# Sheet2.net
KiCad netlist of a schematic drawn in Altium Designer
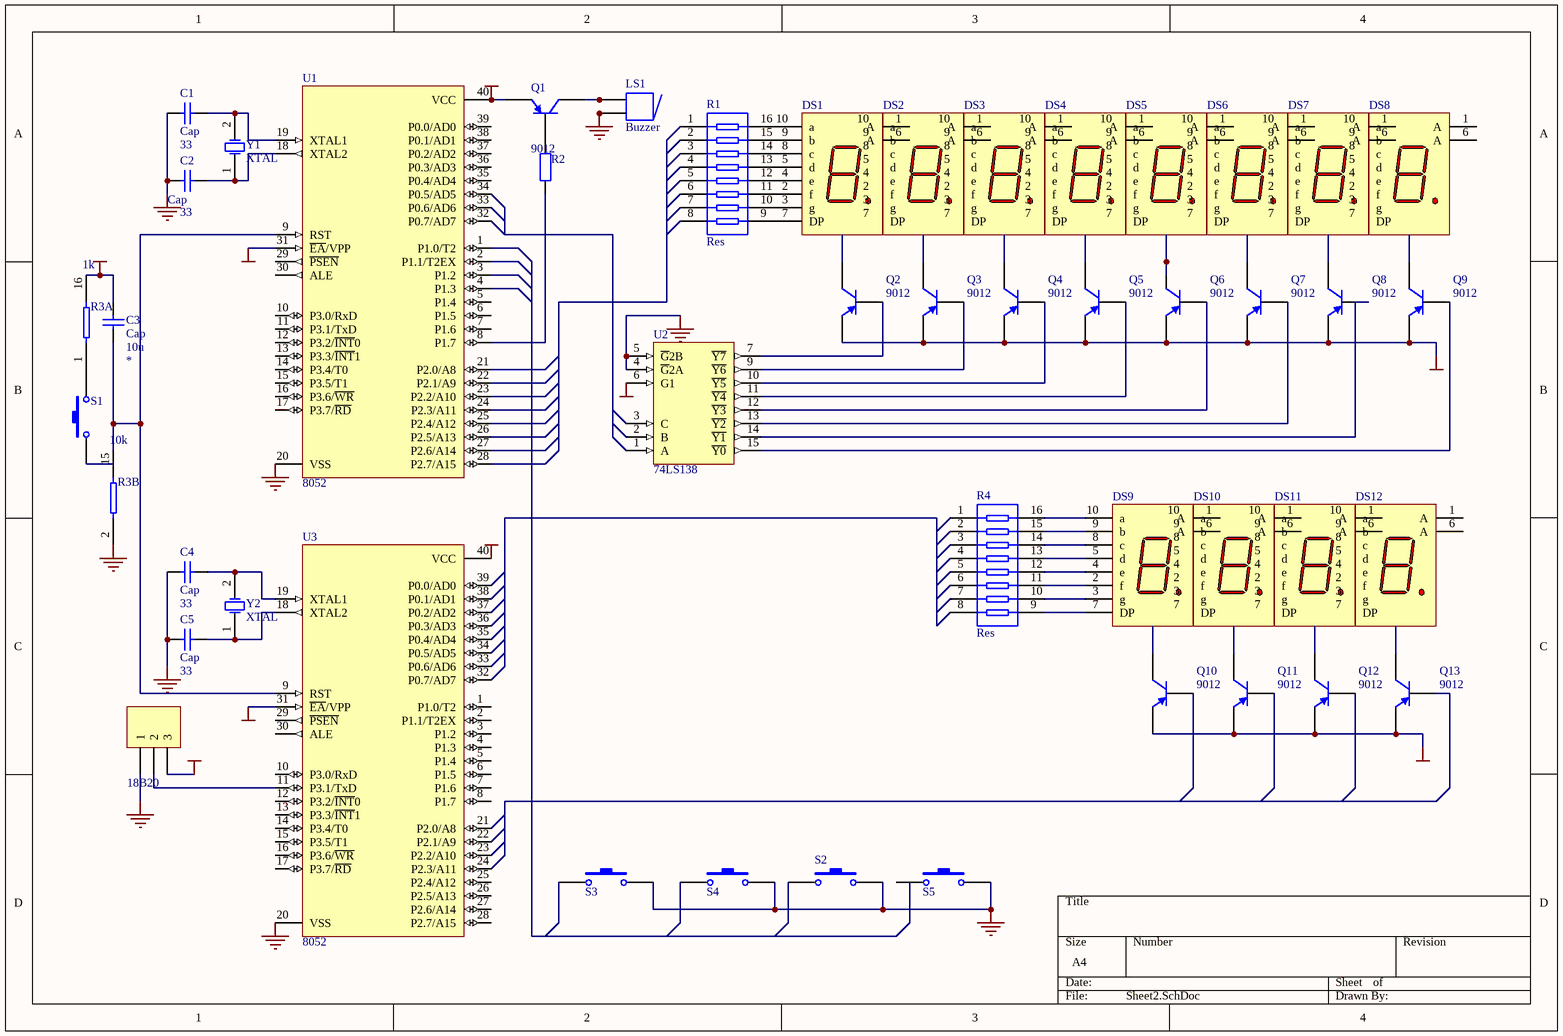
[diagram p0: Sheet2.SchDoc]

(export (version "E")
  (design (tool "Eeschema 10.0.6"))
  (components
    (comp (ref "C1")
      (value "Cap")
      (footprint "RAD-0.3")
      (description "Capacitor")
      (fields (field (name "ALTIUM_UNNAMED_1") "33") (field (name "PUBLISHER") "Altium Limited"))
      (libsource (lib "Miscellaneous Devices") (part "Cap"))
    )
    (comp (ref "C2")
      (value "Cap")
      (footprint "RAD-0.3")
      (description "Capacitor")
      (fields (field (name "ALTIUM_UNNAMED_1") "33") (field (name "PUBLISHER") "Altium Limited"))
      (libsource (lib "Miscellaneous Devices") (part "Cap"))
    )
    (comp (ref "C3")
      (value "Cap")
      (footprint "RAD-0.3")
      (description "Capacitor")
      (fields
        (field (name "ALTIUM_UNNAMED_1") "10u")
        (field (name "ALTIUM_UNNAMED_2") "*")
        (field (name "PUBLISHER") "Altium Limited")
      )
      (libsource (lib "Miscellaneous Devices") (part "Cap"))
    )
    (comp (ref "C4")
      (value "Cap")
      (footprint "RAD-0.3")
      (description "Capacitor")
      (fields (field (name "ALTIUM_UNNAMED_1") "33") (field (name "PUBLISHER") "Altium Limited"))
      (libsource (lib "Miscellaneous Devices") (part "Cap"))
    )
    (comp (ref "C5")
      (value "Cap")
      (footprint "RAD-0.3")
      (description "Capacitor")
      (fields (field (name "ALTIUM_UNNAMED_1") "33") (field (name "PUBLISHER") "Altium Limited"))
      (libsource (lib "Miscellaneous Devices") (part "Cap"))
    )
    (comp (ref "DS1")
      (value "Dpy Red-CA")
      (footprint "LEDDIP-10/C5.08RHD")
      (description "7.62 mm Black Surface HER 7-Segment Display: CA, RH DP")
      (fields (field (name "PUBLISHER") "Altium Limited"))
      (libsource (lib "Miscellaneous Devices") (part "Dpy Red-CA"))
    )
    (comp (ref "DS2")
      (value "Dpy Red-CA")
      (footprint "LEDDIP-10/C5.08RHD")
      (description "7.62 mm Black Surface HER 7-Segment Display: CA, RH DP")
      (fields (field (name "PUBLISHER") "Altium Limited"))
      (libsource (lib "Miscellaneous Devices") (part "Dpy Red-CA"))
    )
    (comp (ref "DS3")
      (value "Dpy Red-CA")
      (footprint "LEDDIP-10/C5.08RHD")
      (description "7.62 mm Black Surface HER 7-Segment Display: CA, RH DP")
      (fields (field (name "PUBLISHER") "Altium Limited"))
      (libsource (lib "Miscellaneous Devices") (part "Dpy Red-CA"))
    )
    (comp (ref "DS4")
      (value "Dpy Red-CA")
      (footprint "LEDDIP-10/C5.08RHD")
      (description "7.62 mm Black Surface HER 7-Segment Display: CA, RH DP")
      (fields (field (name "PUBLISHER") "Altium Limited"))
      (libsource (lib "Miscellaneous Devices") (part "Dpy Red-CA"))
    )
    (comp (ref "DS5")
      (value "Dpy Red-CA")
      (footprint "LEDDIP-10/C5.08RHD")
      (description "7.62 mm Black Surface HER 7-Segment Display: CA, RH DP")
      (fields (field (name "PUBLISHER") "Altium Limited"))
      (libsource (lib "Miscellaneous Devices") (part "Dpy Red-CA"))
    )
    (comp (ref "DS6")
      (value "Dpy Red-CA")
      (footprint "LEDDIP-10/C5.08RHD")
      (description "7.62 mm Black Surface HER 7-Segment Display: CA, RH DP")
      (fields (field (name "PUBLISHER") "Altium Limited"))
      (libsource (lib "Miscellaneous Devices") (part "Dpy Red-CA"))
    )
    (comp (ref "DS7")
      (value "Dpy Red-CA")
      (footprint "LEDDIP-10/C5.08RHD")
      (description "7.62 mm Black Surface HER 7-Segment Display: CA, RH DP")
      (fields (field (name "PUBLISHER") "Altium Limited"))
      (libsource (lib "Miscellaneous Devices") (part "Dpy Red-CA"))
    )
    (comp (ref "DS8")
      (value "Dpy Red-CA")
      (footprint "LEDDIP-10/C5.08RHD")
      (description "7.62 mm Black Surface HER 7-Segment Display: CA, RH DP")
      (fields (field (name "PUBLISHER") "Altium Limited"))
      (libsource (lib "Miscellaneous Devices") (part "Dpy Red-CA"))
    )
    (comp (ref "DS9")
      (value "Dpy Red-CA")
      (footprint "LEDDIP-10/C5.08RHD")
      (description "7.62 mm Black Surface HER 7-Segment Display: CA, RH DP")
      (fields (field (name "PUBLISHER") "Altium Limited"))
      (libsource (lib "Miscellaneous Devices") (part "Dpy Red-CA"))
    )
    (comp (ref "DS10")
      (value "Dpy Red-CA")
      (footprint "LEDDIP-10/C5.08RHD")
      (description "7.62 mm Black Surface HER 7-Segment Display: CA, RH DP")
      (fields (field (name "PUBLISHER") "Altium Limited"))
      (libsource (lib "Miscellaneous Devices") (part "Dpy Red-CA"))
    )
    (comp (ref "DS11")
      (value "Dpy Red-CA")
      (footprint "LEDDIP-10/C5.08RHD")
      (description "7.62 mm Black Surface HER 7-Segment Display: CA, RH DP")
      (fields (field (name "PUBLISHER") "Altium Limited"))
      (libsource (lib "Miscellaneous Devices") (part "Dpy Red-CA"))
    )
    (comp (ref "DS12")
      (value "Dpy Red-CA")
      (footprint "LEDDIP-10/C5.08RHD")
      (description "7.62 mm Black Surface HER 7-Segment Display: CA, RH DP")
      (fields (field (name "PUBLISHER") "Altium Limited"))
      (libsource (lib "Miscellaneous Devices") (part "Dpy Red-CA"))
    )
    (comp (ref "LS1")
      (value "Buzzer")
      (footprint "ABSM-1574")
      (description "Magnetic Transducer Buzzer")
      (fields (field (name "PUBLISHER") "Altium Limited"))
      (libsource (lib "Miscellaneous Devices") (part "Buzzer"))
    )
    (comp (ref "P1")
      (value "18B20")
      (footprint "HDR1X3")
      (description "Header, 3-Pin")
      (fields (field (name "PUBLISHER") "Altium Limited"))
      (libsource (lib "Miscellaneous Connectors") (part "Header 3"))
    )
    (comp (ref "Q1")
      (value "9012")
      (footprint "BCY-W3/E4")
      (description "PNP General Purpose Amplifier")
      (fields (field (name "PUBLISHER") "Altium Limited"))
      (libsource (lib "Miscellaneous Devices") (part "2N3906"))
    )
    (comp (ref "Q2")
      (value "9012")
      (footprint "BCY-W3/E4")
      (description "PNP General Purpose Amplifier")
      (fields (field (name "PUBLISHER") "Altium Limited"))
      (libsource (lib "Miscellaneous Devices") (part "2N3906"))
    )
    (comp (ref "Q3")
      (value "9012")
      (footprint "BCY-W3/E4")
      (description "PNP General Purpose Amplifier")
      (fields (field (name "PUBLISHER") "Altium Limited"))
      (libsource (lib "Miscellaneous Devices") (part "2N3906"))
    )
    (comp (ref "Q4")
      (value "9012")
      (footprint "BCY-W3/E4")
      (description "PNP General Purpose Amplifier")
      (fields (field (name "PUBLISHER") "Altium Limited"))
      (libsource (lib "Miscellaneous Devices") (part "2N3906"))
    )
    (comp (ref "Q5")
      (value "9012")
      (footprint "BCY-W3/E4")
      (description "PNP General Purpose Amplifier")
      (fields (field (name "PUBLISHER") "Altium Limited"))
      (libsource (lib "Miscellaneous Devices") (part "2N3906"))
    )
    (comp (ref "Q6")
      (value "9012")
      (footprint "BCY-W3/E4")
      (description "PNP General Purpose Amplifier")
      (fields (field (name "PUBLISHER") "Altium Limited"))
      (libsource (lib "Miscellaneous Devices") (part "2N3906"))
    )
    (comp (ref "Q7")
      (value "9012")
      (footprint "BCY-W3/E4")
      (description "PNP General Purpose Amplifier")
      (fields (field (name "PUBLISHER") "Altium Limited"))
      (libsource (lib "Miscellaneous Devices") (part "2N3906"))
    )
    (comp (ref "Q8")
      (value "9012")
      (footprint "BCY-W3/E4")
      (description "PNP General Purpose Amplifier")
      (fields (field (name "PUBLISHER") "Altium Limited"))
      (libsource (lib "Miscellaneous Devices") (part "2N3906"))
    )
    (comp (ref "Q9")
      (value "9012")
      (footprint "BCY-W3/E4")
      (description "PNP General Purpose Amplifier")
      (fields (field (name "PUBLISHER") "Altium Limited"))
      (libsource (lib "Miscellaneous Devices") (part "2N3906"))
    )
    (comp (ref "Q10")
      (value "9012")
      (footprint "BCY-W3/E4")
      (description "PNP General Purpose Amplifier")
      (fields (field (name "PUBLISHER") "Altium Limited"))
      (libsource (lib "Miscellaneous Devices") (part "2N3906"))
    )
    (comp (ref "Q11")
      (value "9012")
      (footprint "BCY-W3/E4")
      (description "PNP General Purpose Amplifier")
      (fields (field (name "PUBLISHER") "Altium Limited"))
      (libsource (lib "Miscellaneous Devices") (part "2N3906"))
    )
    (comp (ref "Q12")
      (value "9012")
      (footprint "BCY-W3/E4")
      (description "PNP General Purpose Amplifier")
      (fields (field (name "PUBLISHER") "Altium Limited"))
      (libsource (lib "Miscellaneous Devices") (part "2N3906"))
    )
    (comp (ref "Q13")
      (value "9012")
      (footprint "BCY-W3/E4")
      (description "PNP General Purpose Amplifier")
      (fields (field (name "PUBLISHER") "Altium Limited"))
      (libsource (lib "Miscellaneous Devices") (part "2N3906"))
    )
    (comp (ref "R1")
      (value "Res")
      (footprint "SSO-G16/X.4")
      (description "Isolated Resistor Network")
      (fields (field (name "PUBLISHER") "Altium Limited"))
      (libsource (lib "Miscellaneous Devices") (part "Res Pack4"))
    )
    (comp (ref "R2")
      (value "Res2")
      (footprint "AXIAL-0.4")
      (description "Resistor")
      (fields (field (name "PUBLISHER") "Altium Limited"))
      (libsource (lib "Miscellaneous Devices") (part "Res2"))
    )
    (comp (ref "R3")
      (value "Res Pack2")
      (footprint "DIP-16")
      (description "Isolated Resistor Network - Parts")
      (fields (field (name "ALTIUM_UNNAMED_1") "1k") (field (name "PUBLISHER") "Altium Limited"))
      (libsource (lib "Miscellaneous Devices") (part "Res Pack2"))
    )
    (comp (ref "R4")
      (value "Res")
      (footprint "SSO-G16/X.4")
      (description "Isolated Resistor Network")
      (fields (field (name "PUBLISHER") "Altium Limited"))
      (libsource (lib "Miscellaneous Devices") (part "Res Pack4"))
    )
    (comp (ref "S1")
      (value "SW-PB")
      (footprint "SPST-2")
      (description "Switch")
      (fields (field (name "PUBLISHER") "Altium Limited"))
      (libsource (lib "Miscellaneous Devices") (part "SW-PB"))
    )
    (comp (ref "S2")
      (value "SW-PB")
      (footprint "SPST-2")
      (description "Switch")
      (fields (field (name "PUBLISHER") "Altium Limited"))
      (libsource (lib "Miscellaneous Devices") (part "SW-PB"))
    )
    (comp (ref "S3")
      (value "SW-PB")
      (footprint "SPST-2")
      (description "Switch")
      (fields (field (name "PUBLISHER") "Altium Limited"))
      (libsource (lib "Miscellaneous Devices") (part "SW-PB"))
    )
    (comp (ref "S4")
      (value "SW-PB")
      (footprint "SPST-2")
      (description "Switch")
      (fields (field (name "PUBLISHER") "Altium Limited"))
      (libsource (lib "Miscellaneous Devices") (part "SW-PB"))
    )
    (comp (ref "S5")
      (value "SW-PB")
      (footprint "SPST-2")
      (description "Switch")
      (fields (field (name "PUBLISHER") "Altium Limited"))
      (libsource (lib "Miscellaneous Devices") (part "SW-PB"))
    )
    (comp (ref "U1")
      (value "8052")
      (footprint "SOT129-1")
      (description "80C51 8-Bit Microcontroller Family: 128 B RAM, ROMless, 2.7 V-5.5 V, Low Power, High Speed")
      (fields (field (name "PUBLISHER") "Altium Limited"))
      (libsource (lib "Philips Microcontroller 8-Bit") (part "P80C31SBPN"))
    )
    (comp (ref "U2")
      (value "74LS138")
      (footprint "DIP-16")
      (description "3-Line to 8-Line Decoder/Demultiplexer")
      (libsource (lib "74xx") (part "74LS138"))
    )
    (comp (ref "U3")
      (value "8052")
      (footprint "SOT129-1")
      (description "80C51 8-Bit Microcontroller Family: 128 B RAM, ROMless, 2.7 V-5.5 V, Low Power, High Speed")
      (fields (field (name "PUBLISHER") "Altium Limited"))
      (libsource (lib "Philips Microcontroller 8-Bit") (part "P80C31SBPN"))
    )
    (comp (ref "Y1")
      (value "XTAL")
      (footprint "BCY-W2/D3.1")
      (description "Crystal Oscillator")
      (fields (field (name "PUBLISHER") "Altium Limited"))
      (libsource (lib "Miscellaneous Devices") (part "XTAL"))
    )
    (comp (ref "Y2")
      (value "XTAL")
      (footprint "BCY-W2/D3.1")
      (description "Crystal Oscillator")
      (fields (field (name "PUBLISHER") "Altium Limited"))
      (libsource (lib "Miscellaneous Devices") (part "XTAL"))
    )
  )
  (nets
    (net (code "1") (name "+5") (class "Default")
      (node (ref "P1") (pin "3") (pinfunction "3_3") (pintype "passive"))
      (node (ref "Q10") (pin "1") (pinfunction "E_1") (pintype "passive"))
      (node (ref "Q11") (pin "1") (pinfunction "E_1") (pintype "passive"))
      (node (ref "Q12") (pin "1") (pinfunction "E_1") (pintype "passive"))
      (node (ref "Q13") (pin "1") (pinfunction "E_1") (pintype "passive"))
      (node (ref "Q2") (pin "1") (pinfunction "E_1") (pintype "passive"))
      (node (ref "Q3") (pin "1") (pinfunction "E_1") (pintype "passive"))
      (node (ref "Q4") (pin "1") (pinfunction "E_1") (pintype "passive"))
      (node (ref "Q5") (pin "1") (pinfunction "E_1") (pintype "passive"))
      (node (ref "Q6") (pin "1") (pinfunction "E_1") (pintype "passive"))
      (node (ref "Q7") (pin "1") (pinfunction "E_1") (pintype "passive"))
      (node (ref "Q8") (pin "1") (pinfunction "E_1") (pintype "passive"))
      (node (ref "Q9") (pin "1") (pinfunction "E_1") (pintype "passive"))
      (node (ref "U2") (pin "6") (pinfunction "G1_6") (pintype "input"))
    )
    (net (code "2") (name "+5v") (class "Default")
      (node (ref "C3") (pin "2") (pinfunction "2_2") (pintype "passive"))
      (node (ref "Q1") (pin "1") (pinfunction "E_1") (pintype "passive"))
      (node (ref "R3") (pin "16") (pinfunction "16_16") (pintype "passive"))
      (node (ref "U1") (pin "31") (pinfunction "~{EA}/VPP_31") (pintype "input"))
      (node (ref "U1") (pin "40") (pinfunction "VCC_40") (pintype "power_in"))
      (node (ref "U3") (pin "31") (pinfunction "~{EA}/VPP_31") (pintype "input"))
      (node (ref "U3") (pin "40") (pinfunction "VCC_40") (pintype "power_in"))
    )
    (net (code "3") (name "GND") (class "Default")
      (node (ref "C1") (pin "2") (pinfunction "2_2") (pintype "passive"))
      (node (ref "C2") (pin "2") (pinfunction "2_2") (pintype "passive"))
      (node (ref "C4") (pin "2") (pinfunction "2_2") (pintype "passive"))
      (node (ref "C5") (pin "2") (pinfunction "2_2") (pintype "passive"))
      (node (ref "LS1") (pin "1") (pinfunction "1_1") (pintype "passive"))
      (node (ref "LS1") (pin "1A") (pinfunction "1A_1A") (pintype "passive"))
      (node (ref "P1") (pin "1") (pinfunction "1_1") (pintype "passive"))
      (node (ref "R3") (pin "2") (pinfunction "2_2") (pintype "passive"))
      (node (ref "S2") (pin "2") (pinfunction "2_2") (pintype "passive"))
      (node (ref "S3") (pin "2") (pinfunction "2_2") (pintype "passive"))
      (node (ref "S4") (pin "2") (pinfunction "2_2") (pintype "passive"))
      (node (ref "S5") (pin "2") (pinfunction "2_2") (pintype "passive"))
      (node (ref "U1") (pin "20") (pinfunction "VSS_20") (pintype "power_in"))
      (node (ref "U2") (pin "4") (pinfunction "~{G}2A_4") (pintype "input"))
      (node (ref "U2") (pin "5") (pinfunction "~{G}2B_5") (pintype "input"))
      (node (ref "U2") (pin "8") (pinfunction "GND_8") (pintype "power_in"))
      (node (ref "U3") (pin "20") (pinfunction "VSS_20") (pintype "power_in"))
    )
    (net (code "4") (name "Net-(DS1-DP)") (class "Default")
      (node (ref "DS1") (pin "7") (pinfunction "DP_7") (pintype "passive"))
      (node (ref "R1") (pin "9") (pinfunction "9_9") (pintype "passive"))
    )
    (net (code "5") (name "Net-(DS1-a)") (class "Default")
      (node (ref "DS1") (pin "10") (pinfunction "a_10") (pintype "passive"))
      (node (ref "R1") (pin "16") (pinfunction "16_16") (pintype "passive"))
    )
    (net (code "6") (name "Net-(DS1-b)") (class "Default")
      (node (ref "DS1") (pin "9") (pinfunction "b_9") (pintype "passive"))
      (node (ref "R1") (pin "15") (pinfunction "15_15") (pintype "passive"))
    )
    (net (code "7") (name "Net-(DS1-c)") (class "Default")
      (node (ref "DS1") (pin "8") (pinfunction "c_8") (pintype "passive"))
      (node (ref "R1") (pin "14") (pinfunction "14_14") (pintype "passive"))
    )
    (net (code "8") (name "Net-(DS1-d)") (class "Default")
      (node (ref "DS1") (pin "5") (pinfunction "d_5") (pintype "passive"))
      (node (ref "R1") (pin "13") (pinfunction "13_13") (pintype "passive"))
    )
    (net (code "9") (name "Net-(DS1-e)") (class "Default")
      (node (ref "DS1") (pin "4") (pinfunction "e_4") (pintype "passive"))
      (node (ref "R1") (pin "12") (pinfunction "12_12") (pintype "passive"))
    )
    (net (code "10") (name "Net-(DS1-f)") (class "Default")
      (node (ref "DS1") (pin "2") (pinfunction "f_2") (pintype "passive"))
      (node (ref "R1") (pin "11") (pinfunction "11_11") (pintype "passive"))
    )
    (net (code "11") (name "Net-(DS1-g)") (class "Default")
      (node (ref "DS1") (pin "3") (pinfunction "g_3") (pintype "passive"))
      (node (ref "R1") (pin "10") (pinfunction "10_10") (pintype "passive"))
    )
    (net (code "12") (name "Net-(DS9-DP)") (class "Default")
      (node (ref "DS9") (pin "7") (pinfunction "DP_7") (pintype "passive"))
      (node (ref "R4") (pin "9") (pinfunction "9_9") (pintype "passive"))
    )
    (net (code "13") (name "Net-(DS9-a)") (class "Default")
      (node (ref "DS9") (pin "10") (pinfunction "a_10") (pintype "passive"))
      (node (ref "R4") (pin "16") (pinfunction "16_16") (pintype "passive"))
    )
    (net (code "14") (name "Net-(DS9-b)") (class "Default")
      (node (ref "DS9") (pin "9") (pinfunction "b_9") (pintype "passive"))
      (node (ref "R4") (pin "15") (pinfunction "15_15") (pintype "passive"))
    )
    (net (code "15") (name "Net-(DS9-c)") (class "Default")
      (node (ref "DS9") (pin "8") (pinfunction "c_8") (pintype "passive"))
      (node (ref "R4") (pin "14") (pinfunction "14_14") (pintype "passive"))
    )
    (net (code "16") (name "Net-(DS9-d)") (class "Default")
      (node (ref "DS9") (pin "5") (pinfunction "d_5") (pintype "passive"))
      (node (ref "R4") (pin "13") (pinfunction "13_13") (pintype "passive"))
    )
    (net (code "17") (name "Net-(DS9-e)") (class "Default")
      (node (ref "DS9") (pin "4") (pinfunction "e_4") (pintype "passive"))
      (node (ref "R4") (pin "12") (pinfunction "12_12") (pintype "passive"))
    )
    (net (code "18") (name "Net-(DS9-f)") (class "Default")
      (node (ref "DS9") (pin "2") (pinfunction "f_2") (pintype "passive"))
      (node (ref "R4") (pin "11") (pinfunction "11_11") (pintype "passive"))
    )
    (net (code "19") (name "Net-(DS9-g)") (class "Default")
      (node (ref "DS9") (pin "3") (pinfunction "g_3") (pintype "passive"))
      (node (ref "R4") (pin "10") (pinfunction "10_10") (pintype "passive"))
    )
    (net (code "20") (name "Net-(Q1-B)") (class "Default")
      (node (ref "Q1") (pin "2") (pinfunction "B_2") (pintype "passive"))
      (node (ref "R2") (pin "2") (pinfunction "2_2") (pintype "passive"))
    )
    (net (code "21") (name "Net-(Q1-C)") (class "Default")
      (node (ref "LS1") (pin "2") (pinfunction "2_2") (pintype "passive"))
      (node (ref "LS1") (pin "2A") (pinfunction "2A_2A") (pintype "passive"))
      (node (ref "Q1") (pin "3") (pinfunction "C_3") (pintype "passive"))
    )
    (net (code "22") (name "Net-(Q2-B)") (class "Default")
      (node (ref "Q2") (pin "2") (pinfunction "B_2") (pintype "passive"))
      (node (ref "U2") (pin "7") (pinfunction "~{Y7}_7") (pintype "output"))
    )
    (net (code "23") (name "Net-(Q3-B)") (class "Default")
      (node (ref "Q3") (pin "2") (pinfunction "B_2") (pintype "passive"))
      (node (ref "U2") (pin "9") (pinfunction "~{Y6}_9") (pintype "output"))
    )
    (net (code "24") (name "Net-(Q4-B)") (class "Default")
      (node (ref "Q4") (pin "2") (pinfunction "B_2") (pintype "passive"))
      (node (ref "U2") (pin "10") (pinfunction "~{Y5}_10") (pintype "output"))
    )
    (net (code "25") (name "Net-(Q5-B)") (class "Default")
      (node (ref "Q5") (pin "2") (pinfunction "B_2") (pintype "passive"))
      (node (ref "U2") (pin "11") (pinfunction "~{Y4}_11") (pintype "output"))
    )
    (net (code "26") (name "Net-(Q6-B)") (class "Default")
      (node (ref "Q6") (pin "2") (pinfunction "B_2") (pintype "passive"))
      (node (ref "U2") (pin "12") (pinfunction "~{Y3}_12") (pintype "output"))
    )
    (net (code "27") (name "Net-(Q7-B)") (class "Default")
      (node (ref "Q7") (pin "2") (pinfunction "B_2") (pintype "passive"))
      (node (ref "U2") (pin "13") (pinfunction "~{Y2}_13") (pintype "output"))
    )
    (net (code "28") (name "Net-(Q8-B)") (class "Default")
      (node (ref "Q8") (pin "2") (pinfunction "B_2") (pintype "passive"))
      (node (ref "U2") (pin "14") (pinfunction "~{Y1}_14") (pintype "output"))
    )
    (net (code "29") (name "Net-(Q9-B)") (class "Default")
      (node (ref "Q9") (pin "2") (pinfunction "B_2") (pintype "passive"))
      (node (ref "U2") (pin "15") (pinfunction "~{Y0}_15") (pintype "output"))
    )
    (net (code "30") (name "Net-(R3-Pad1)") (class "Default")
      (node (ref "R3") (pin "1") (pinfunction "1_1") (pintype "passive"))
      (node (ref "S1") (pin "2") (pinfunction "2_2") (pintype "passive"))
    )
    (net (code "31") (name "Net-(U1-P1.7)") (class "Default")
      (node (ref "R2") (pin "1") (pinfunction "1_1") (pintype "passive"))
      (node (ref "U1") (pin "8") (pinfunction "P1.7_8") (pintype "bidirectional"))
    )
    (net (code "32") (name "Net-(U1-RST)") (class "Default")
      (node (ref "C3") (pin "1") (pinfunction "1_1") (pintype "passive"))
      (node (ref "R3") (pin "15") (pinfunction "15_15") (pintype "passive"))
      (node (ref "U1") (pin "9") (pinfunction "RST_9") (pintype "input"))
      (node (ref "U3") (pin "9") (pinfunction "RST_9") (pintype "input"))
    )
    (net (code "33") (name "Net-(U1-XTAL1)") (class "Default")
      (node (ref "C1") (pin "1") (pinfunction "1_1") (pintype "passive"))
      (node (ref "U1") (pin "19") (pinfunction "XTAL1_19") (pintype "input"))
      (node (ref "Y1") (pin "2") (pinfunction "OSC2_2") (pintype "passive"))
    )
    (net (code "34") (name "Net-(U1-XTAL2)") (class "Default")
      (node (ref "C2") (pin "1") (pinfunction "1_1") (pintype "passive"))
      (node (ref "U1") (pin "18") (pinfunction "XTAL2_18") (pintype "output"))
      (node (ref "Y1") (pin "1") (pinfunction "OSC1_1") (pintype "passive"))
    )
    (net (code "35") (name "Net-(U3-P3.1{slash}TxD)") (class "Default")
      (node (ref "P1") (pin "2") (pinfunction "2_2") (pintype "passive"))
      (node (ref "U3") (pin "11") (pinfunction "P3.1/TxD_11") (pintype "bidirectional"))
    )
    (net (code "36") (name "Net-(U3-XTAL1)") (class "Default")
      (node (ref "C4") (pin "1") (pinfunction "1_1") (pintype "passive"))
      (node (ref "U3") (pin "19") (pinfunction "XTAL1_19") (pintype "input"))
      (node (ref "Y2") (pin "2") (pinfunction "OSC2_2") (pintype "passive"))
    )
    (net (code "37") (name "Net-(U3-XTAL2)") (class "Default")
      (node (ref "C5") (pin "1") (pinfunction "1_1") (pintype "passive"))
      (node (ref "U3") (pin "18") (pinfunction "XTAL2_18") (pintype "output"))
      (node (ref "Y2") (pin "1") (pinfunction "OSC1_1") (pintype "passive"))
    )
    (net (code "38") (name "VCC") (class "Default")
      (node (ref "U2") (pin "16") (pinfunction "VCC_16") (pintype "power_in"))
    )
    (net (code "39") (name "unconnected-(DS1-A-Pad1)") (class "Default")
      (node (ref "DS1") (pin "1") (pinfunction "A_1") (pintype "passive"))
    )
    (net (code "40") (name "unconnected-(DS1-A-Pad6)") (class "Default")
      (node (ref "DS1") (pin "6") (pinfunction "A_6") (pintype "passive"))
    )
    (net (code "41") (name "unconnected-(DS2-A-Pad1)") (class "Default")
      (node (ref "DS2") (pin "1") (pinfunction "A_1") (pintype "passive"))
    )
    (net (code "42") (name "unconnected-(DS2-A-Pad6)") (class "Default")
      (node (ref "DS2") (pin "6") (pinfunction "A_6") (pintype "passive"))
    )
    (net (code "43") (name "unconnected-(DS2-DP-Pad7)") (class "Default")
      (node (ref "DS2") (pin "7") (pinfunction "DP_7") (pintype "passive"))
    )
    (net (code "44") (name "unconnected-(DS2-a-Pad10)") (class "Default")
      (node (ref "DS2") (pin "10") (pinfunction "a_10") (pintype "passive"))
    )
    (net (code "45") (name "unconnected-(DS2-b-Pad9)") (class "Default")
      (node (ref "DS2") (pin "9") (pinfunction "b_9") (pintype "passive"))
    )
    (net (code "46") (name "unconnected-(DS2-c-Pad8)") (class "Default")
      (node (ref "DS2") (pin "8") (pinfunction "c_8") (pintype "passive"))
    )
    (net (code "47") (name "unconnected-(DS2-d-Pad5)") (class "Default")
      (node (ref "DS2") (pin "5") (pinfunction "d_5") (pintype "passive"))
    )
    (net (code "48") (name "unconnected-(DS2-e-Pad4)") (class "Default")
      (node (ref "DS2") (pin "4") (pinfunction "e_4") (pintype "passive"))
    )
    (net (code "49") (name "unconnected-(DS2-f-Pad2)") (class "Default")
      (node (ref "DS2") (pin "2") (pinfunction "f_2") (pintype "passive"))
    )
    (net (code "50") (name "unconnected-(DS2-g-Pad3)") (class "Default")
      (node (ref "DS2") (pin "3") (pinfunction "g_3") (pintype "passive"))
    )
    (net (code "51") (name "unconnected-(DS3-A-Pad1)") (class "Default")
      (node (ref "DS3") (pin "1") (pinfunction "A_1") (pintype "passive"))
    )
    (net (code "52") (name "unconnected-(DS3-A-Pad6)") (class "Default")
      (node (ref "DS3") (pin "6") (pinfunction "A_6") (pintype "passive"))
    )
    (net (code "53") (name "unconnected-(DS3-DP-Pad7)") (class "Default")
      (node (ref "DS3") (pin "7") (pinfunction "DP_7") (pintype "passive"))
    )
    (net (code "54") (name "unconnected-(DS3-a-Pad10)") (class "Default")
      (node (ref "DS3") (pin "10") (pinfunction "a_10") (pintype "passive"))
    )
    (net (code "55") (name "unconnected-(DS3-b-Pad9)") (class "Default")
      (node (ref "DS3") (pin "9") (pinfunction "b_9") (pintype "passive"))
    )
    (net (code "56") (name "unconnected-(DS3-c-Pad8)") (class "Default")
      (node (ref "DS3") (pin "8") (pinfunction "c_8") (pintype "passive"))
    )
    (net (code "57") (name "unconnected-(DS3-d-Pad5)") (class "Default")
      (node (ref "DS3") (pin "5") (pinfunction "d_5") (pintype "passive"))
    )
    (net (code "58") (name "unconnected-(DS3-e-Pad4)") (class "Default")
      (node (ref "DS3") (pin "4") (pinfunction "e_4") (pintype "passive"))
    )
    (net (code "59") (name "unconnected-(DS3-f-Pad2)") (class "Default")
      (node (ref "DS3") (pin "2") (pinfunction "f_2") (pintype "passive"))
    )
    (net (code "60") (name "unconnected-(DS3-g-Pad3)") (class "Default")
      (node (ref "DS3") (pin "3") (pinfunction "g_3") (pintype "passive"))
    )
    (net (code "61") (name "unconnected-(DS4-A-Pad1)") (class "Default")
      (node (ref "DS4") (pin "1") (pinfunction "A_1") (pintype "passive"))
    )
    (net (code "62") (name "unconnected-(DS4-A-Pad6)") (class "Default")
      (node (ref "DS4") (pin "6") (pinfunction "A_6") (pintype "passive"))
    )
    (net (code "63") (name "unconnected-(DS4-DP-Pad7)") (class "Default")
      (node (ref "DS4") (pin "7") (pinfunction "DP_7") (pintype "passive"))
    )
    (net (code "64") (name "unconnected-(DS4-a-Pad10)") (class "Default")
      (node (ref "DS4") (pin "10") (pinfunction "a_10") (pintype "passive"))
    )
    (net (code "65") (name "unconnected-(DS4-b-Pad9)") (class "Default")
      (node (ref "DS4") (pin "9") (pinfunction "b_9") (pintype "passive"))
    )
    (net (code "66") (name "unconnected-(DS4-c-Pad8)") (class "Default")
      (node (ref "DS4") (pin "8") (pinfunction "c_8") (pintype "passive"))
    )
    (net (code "67") (name "unconnected-(DS4-d-Pad5)") (class "Default")
      (node (ref "DS4") (pin "5") (pinfunction "d_5") (pintype "passive"))
    )
    (net (code "68") (name "unconnected-(DS4-e-Pad4)") (class "Default")
      (node (ref "DS4") (pin "4") (pinfunction "e_4") (pintype "passive"))
    )
    (net (code "69") (name "unconnected-(DS4-f-Pad2)") (class "Default")
      (node (ref "DS4") (pin "2") (pinfunction "f_2") (pintype "passive"))
    )
    (net (code "70") (name "unconnected-(DS4-g-Pad3)") (class "Default")
      (node (ref "DS4") (pin "3") (pinfunction "g_3") (pintype "passive"))
    )
    (net (code "71") (name "unconnected-(DS5-A-Pad1)") (class "Default")
      (node (ref "DS5") (pin "1") (pinfunction "A_1") (pintype "passive"))
    )
    (net (code "72") (name "unconnected-(DS5-A-Pad6)") (class "Default")
      (node (ref "DS5") (pin "6") (pinfunction "A_6") (pintype "passive"))
    )
    (net (code "73") (name "unconnected-(DS5-DP-Pad7)") (class "Default")
      (node (ref "DS5") (pin "7") (pinfunction "DP_7") (pintype "passive"))
    )
    (net (code "74") (name "unconnected-(DS5-a-Pad10)") (class "Default")
      (node (ref "DS5") (pin "10") (pinfunction "a_10") (pintype "passive"))
    )
    (net (code "75") (name "unconnected-(DS5-b-Pad9)") (class "Default")
      (node (ref "DS5") (pin "9") (pinfunction "b_9") (pintype "passive"))
    )
    (net (code "76") (name "unconnected-(DS5-c-Pad8)") (class "Default")
      (node (ref "DS5") (pin "8") (pinfunction "c_8") (pintype "passive"))
    )
    (net (code "77") (name "unconnected-(DS5-d-Pad5)") (class "Default")
      (node (ref "DS5") (pin "5") (pinfunction "d_5") (pintype "passive"))
    )
    (net (code "78") (name "unconnected-(DS5-e-Pad4)") (class "Default")
      (node (ref "DS5") (pin "4") (pinfunction "e_4") (pintype "passive"))
    )
    (net (code "79") (name "unconnected-(DS5-f-Pad2)") (class "Default")
      (node (ref "DS5") (pin "2") (pinfunction "f_2") (pintype "passive"))
    )
    (net (code "80") (name "unconnected-(DS5-g-Pad3)") (class "Default")
      (node (ref "DS5") (pin "3") (pinfunction "g_3") (pintype "passive"))
    )
    (net (code "81") (name "unconnected-(DS6-A-Pad1)") (class "Default")
      (node (ref "DS6") (pin "1") (pinfunction "A_1") (pintype "passive"))
    )
    (net (code "82") (name "unconnected-(DS6-A-Pad6)") (class "Default")
      (node (ref "DS6") (pin "6") (pinfunction "A_6") (pintype "passive"))
    )
    (net (code "83") (name "unconnected-(DS6-DP-Pad7)") (class "Default")
      (node (ref "DS6") (pin "7") (pinfunction "DP_7") (pintype "passive"))
    )
    (net (code "84") (name "unconnected-(DS6-a-Pad10)") (class "Default")
      (node (ref "DS6") (pin "10") (pinfunction "a_10") (pintype "passive"))
    )
    (net (code "85") (name "unconnected-(DS6-b-Pad9)") (class "Default")
      (node (ref "DS6") (pin "9") (pinfunction "b_9") (pintype "passive"))
    )
    (net (code "86") (name "unconnected-(DS6-c-Pad8)") (class "Default")
      (node (ref "DS6") (pin "8") (pinfunction "c_8") (pintype "passive"))
    )
    (net (code "87") (name "unconnected-(DS6-d-Pad5)") (class "Default")
      (node (ref "DS6") (pin "5") (pinfunction "d_5") (pintype "passive"))
    )
    (net (code "88") (name "unconnected-(DS6-e-Pad4)") (class "Default")
      (node (ref "DS6") (pin "4") (pinfunction "e_4") (pintype "passive"))
    )
    (net (code "89") (name "unconnected-(DS6-f-Pad2)") (class "Default")
      (node (ref "DS6") (pin "2") (pinfunction "f_2") (pintype "passive"))
    )
    (net (code "90") (name "unconnected-(DS6-g-Pad3)") (class "Default")
      (node (ref "DS6") (pin "3") (pinfunction "g_3") (pintype "passive"))
    )
    (net (code "91") (name "unconnected-(DS7-A-Pad1)") (class "Default")
      (node (ref "DS7") (pin "1") (pinfunction "A_1") (pintype "passive"))
    )
    (net (code "92") (name "unconnected-(DS7-A-Pad6)") (class "Default")
      (node (ref "DS7") (pin "6") (pinfunction "A_6") (pintype "passive"))
    )
    (net (code "93") (name "unconnected-(DS7-DP-Pad7)") (class "Default")
      (node (ref "DS7") (pin "7") (pinfunction "DP_7") (pintype "passive"))
    )
    (net (code "94") (name "unconnected-(DS7-a-Pad10)") (class "Default")
      (node (ref "DS7") (pin "10") (pinfunction "a_10") (pintype "passive"))
    )
    (net (code "95") (name "unconnected-(DS7-b-Pad9)") (class "Default")
      (node (ref "DS7") (pin "9") (pinfunction "b_9") (pintype "passive"))
    )
    (net (code "96") (name "unconnected-(DS7-c-Pad8)") (class "Default")
      (node (ref "DS7") (pin "8") (pinfunction "c_8") (pintype "passive"))
    )
    (net (code "97") (name "unconnected-(DS7-d-Pad5)") (class "Default")
      (node (ref "DS7") (pin "5") (pinfunction "d_5") (pintype "passive"))
    )
    (net (code "98") (name "unconnected-(DS7-e-Pad4)") (class "Default")
      (node (ref "DS7") (pin "4") (pinfunction "e_4") (pintype "passive"))
    )
    (net (code "99") (name "unconnected-(DS7-f-Pad2)") (class "Default")
      (node (ref "DS7") (pin "2") (pinfunction "f_2") (pintype "passive"))
    )
    (net (code "100") (name "unconnected-(DS7-g-Pad3)") (class "Default")
      (node (ref "DS7") (pin "3") (pinfunction "g_3") (pintype "passive"))
    )
    (net (code "101") (name "unconnected-(DS8-A-Pad1)") (class "Default")
      (node (ref "DS8") (pin "1") (pinfunction "A_1") (pintype "passive"))
    )
    (net (code "102") (name "unconnected-(DS8-A-Pad6)") (class "Default")
      (node (ref "DS8") (pin "6") (pinfunction "A_6") (pintype "passive"))
    )
    (net (code "103") (name "unconnected-(DS8-DP-Pad7)") (class "Default")
      (node (ref "DS8") (pin "7") (pinfunction "DP_7") (pintype "passive"))
    )
    (net (code "104") (name "unconnected-(DS8-a-Pad10)") (class "Default")
      (node (ref "DS8") (pin "10") (pinfunction "a_10") (pintype "passive"))
    )
    (net (code "105") (name "unconnected-(DS8-b-Pad9)") (class "Default")
      (node (ref "DS8") (pin "9") (pinfunction "b_9") (pintype "passive"))
    )
    (net (code "106") (name "unconnected-(DS8-c-Pad8)") (class "Default")
      (node (ref "DS8") (pin "8") (pinfunction "c_8") (pintype "passive"))
    )
    (net (code "107") (name "unconnected-(DS8-d-Pad5)") (class "Default")
      (node (ref "DS8") (pin "5") (pinfunction "d_5") (pintype "passive"))
    )
    (net (code "108") (name "unconnected-(DS8-e-Pad4)") (class "Default")
      (node (ref "DS8") (pin "4") (pinfunction "e_4") (pintype "passive"))
    )
    (net (code "109") (name "unconnected-(DS8-f-Pad2)") (class "Default")
      (node (ref "DS8") (pin "2") (pinfunction "f_2") (pintype "passive"))
    )
    (net (code "110") (name "unconnected-(DS8-g-Pad3)") (class "Default")
      (node (ref "DS8") (pin "3") (pinfunction "g_3") (pintype "passive"))
    )
    (net (code "111") (name "unconnected-(DS9-A-Pad1)") (class "Default")
      (node (ref "DS9") (pin "1") (pinfunction "A_1") (pintype "passive"))
    )
    (net (code "112") (name "unconnected-(DS9-A-Pad6)") (class "Default")
      (node (ref "DS9") (pin "6") (pinfunction "A_6") (pintype "passive"))
    )
    (net (code "113") (name "unconnected-(DS10-A-Pad1)") (class "Default")
      (node (ref "DS10") (pin "1") (pinfunction "A_1") (pintype "passive"))
    )
    (net (code "114") (name "unconnected-(DS10-A-Pad6)") (class "Default")
      (node (ref "DS10") (pin "6") (pinfunction "A_6") (pintype "passive"))
    )
    (net (code "115") (name "unconnected-(DS10-DP-Pad7)") (class "Default")
      (node (ref "DS10") (pin "7") (pinfunction "DP_7") (pintype "passive"))
    )
    (net (code "116") (name "unconnected-(DS10-a-Pad10)") (class "Default")
      (node (ref "DS10") (pin "10") (pinfunction "a_10") (pintype "passive"))
    )
    (net (code "117") (name "unconnected-(DS10-b-Pad9)") (class "Default")
      (node (ref "DS10") (pin "9") (pinfunction "b_9") (pintype "passive"))
    )
    (net (code "118") (name "unconnected-(DS10-c-Pad8)") (class "Default")
      (node (ref "DS10") (pin "8") (pinfunction "c_8") (pintype "passive"))
    )
    (net (code "119") (name "unconnected-(DS10-d-Pad5)") (class "Default")
      (node (ref "DS10") (pin "5") (pinfunction "d_5") (pintype "passive"))
    )
    (net (code "120") (name "unconnected-(DS10-e-Pad4)") (class "Default")
      (node (ref "DS10") (pin "4") (pinfunction "e_4") (pintype "passive"))
    )
    (net (code "121") (name "unconnected-(DS10-f-Pad2)") (class "Default")
      (node (ref "DS10") (pin "2") (pinfunction "f_2") (pintype "passive"))
    )
    (net (code "122") (name "unconnected-(DS10-g-Pad3)") (class "Default")
      (node (ref "DS10") (pin "3") (pinfunction "g_3") (pintype "passive"))
    )
    (net (code "123") (name "unconnected-(DS11-A-Pad1)") (class "Default")
      (node (ref "DS11") (pin "1") (pinfunction "A_1") (pintype "passive"))
    )
    (net (code "124") (name "unconnected-(DS11-A-Pad6)") (class "Default")
      (node (ref "DS11") (pin "6") (pinfunction "A_6") (pintype "passive"))
    )
    (net (code "125") (name "unconnected-(DS11-DP-Pad7)") (class "Default")
      (node (ref "DS11") (pin "7") (pinfunction "DP_7") (pintype "passive"))
    )
    (net (code "126") (name "unconnected-(DS11-a-Pad10)") (class "Default")
      (node (ref "DS11") (pin "10") (pinfunction "a_10") (pintype "passive"))
    )
    (net (code "127") (name "unconnected-(DS11-b-Pad9)") (class "Default")
      (node (ref "DS11") (pin "9") (pinfunction "b_9") (pintype "passive"))
    )
    (net (code "128") (name "unconnected-(DS11-c-Pad8)") (class "Default")
      (node (ref "DS11") (pin "8") (pinfunction "c_8") (pintype "passive"))
    )
    (net (code "129") (name "unconnected-(DS11-d-Pad5)") (class "Default")
      (node (ref "DS11") (pin "5") (pinfunction "d_5") (pintype "passive"))
    )
    (net (code "130") (name "unconnected-(DS11-e-Pad4)") (class "Default")
      (node (ref "DS11") (pin "4") (pinfunction "e_4") (pintype "passive"))
    )
    (net (code "131") (name "unconnected-(DS11-f-Pad2)") (class "Default")
      (node (ref "DS11") (pin "2") (pinfunction "f_2") (pintype "passive"))
    )
    (net (code "132") (name "unconnected-(DS11-g-Pad3)") (class "Default")
      (node (ref "DS11") (pin "3") (pinfunction "g_3") (pintype "passive"))
    )
    (net (code "133") (name "unconnected-(DS12-A-Pad1)") (class "Default")
      (node (ref "DS12") (pin "1") (pinfunction "A_1") (pintype "passive"))
    )
    (net (code "134") (name "unconnected-(DS12-A-Pad6)") (class "Default")
      (node (ref "DS12") (pin "6") (pinfunction "A_6") (pintype "passive"))
    )
    (net (code "135") (name "unconnected-(DS12-DP-Pad7)") (class "Default")
      (node (ref "DS12") (pin "7") (pinfunction "DP_7") (pintype "passive"))
    )
    (net (code "136") (name "unconnected-(DS12-a-Pad10)") (class "Default")
      (node (ref "DS12") (pin "10") (pinfunction "a_10") (pintype "passive"))
    )
    (net (code "137") (name "unconnected-(DS12-b-Pad9)") (class "Default")
      (node (ref "DS12") (pin "9") (pinfunction "b_9") (pintype "passive"))
    )
    (net (code "138") (name "unconnected-(DS12-c-Pad8)") (class "Default")
      (node (ref "DS12") (pin "8") (pinfunction "c_8") (pintype "passive"))
    )
    (net (code "139") (name "unconnected-(DS12-d-Pad5)") (class "Default")
      (node (ref "DS12") (pin "5") (pinfunction "d_5") (pintype "passive"))
    )
    (net (code "140") (name "unconnected-(DS12-e-Pad4)") (class "Default")
      (node (ref "DS12") (pin "4") (pinfunction "e_4") (pintype "passive"))
    )
    (net (code "141") (name "unconnected-(DS12-f-Pad2)") (class "Default")
      (node (ref "DS12") (pin "2") (pinfunction "f_2") (pintype "passive"))
    )
    (net (code "142") (name "unconnected-(DS12-g-Pad3)") (class "Default")
      (node (ref "DS12") (pin "3") (pinfunction "g_3") (pintype "passive"))
    )
    (net (code "143") (name "unconnected-(Q2-C-Pad3)") (class "Default")
      (node (ref "Q2") (pin "3") (pinfunction "C_3") (pintype "passive"))
    )
    (net (code "144") (name "unconnected-(Q3-C-Pad3)") (class "Default")
      (node (ref "Q3") (pin "3") (pinfunction "C_3") (pintype "passive"))
    )
    (net (code "145") (name "unconnected-(Q4-C-Pad3)") (class "Default")
      (node (ref "Q4") (pin "3") (pinfunction "C_3") (pintype "passive"))
    )
    (net (code "146") (name "unconnected-(Q5-C-Pad3)") (class "Default")
      (node (ref "Q5") (pin "3") (pinfunction "C_3") (pintype "passive"))
    )
    (net (code "147") (name "unconnected-(Q6-C-Pad3)") (class "Default")
      (node (ref "Q6") (pin "3") (pinfunction "C_3") (pintype "passive"))
    )
    (net (code "148") (name "unconnected-(Q7-C-Pad3)") (class "Default")
      (node (ref "Q7") (pin "3") (pinfunction "C_3") (pintype "passive"))
    )
    (net (code "149") (name "unconnected-(Q8-C-Pad3)") (class "Default")
      (node (ref "Q8") (pin "3") (pinfunction "C_3") (pintype "passive"))
    )
    (net (code "150") (name "unconnected-(Q9-C-Pad3)") (class "Default")
      (node (ref "Q9") (pin "3") (pinfunction "C_3") (pintype "passive"))
    )
    (net (code "151") (name "unconnected-(Q10-B-Pad2)") (class "Default")
      (node (ref "Q10") (pin "2") (pinfunction "B_2") (pintype "passive"))
    )
    (net (code "152") (name "unconnected-(Q10-C-Pad3)") (class "Default")
      (node (ref "Q10") (pin "3") (pinfunction "C_3") (pintype "passive"))
    )
    (net (code "153") (name "unconnected-(Q11-B-Pad2)") (class "Default")
      (node (ref "Q11") (pin "2") (pinfunction "B_2") (pintype "passive"))
    )
    (net (code "154") (name "unconnected-(Q11-C-Pad3)") (class "Default")
      (node (ref "Q11") (pin "3") (pinfunction "C_3") (pintype "passive"))
    )
    (net (code "155") (name "unconnected-(Q12-B-Pad2)") (class "Default")
      (node (ref "Q12") (pin "2") (pinfunction "B_2") (pintype "passive"))
    )
    (net (code "156") (name "unconnected-(Q12-C-Pad3)") (class "Default")
      (node (ref "Q12") (pin "3") (pinfunction "C_3") (pintype "passive"))
    )
    (net (code "157") (name "unconnected-(Q13-B-Pad2)") (class "Default")
      (node (ref "Q13") (pin "2") (pinfunction "B_2") (pintype "passive"))
    )
    (net (code "158") (name "unconnected-(Q13-C-Pad3)") (class "Default")
      (node (ref "Q13") (pin "3") (pinfunction "C_3") (pintype "passive"))
    )
    (net (code "159") (name "unconnected-(R1-Pad1)") (class "Default")
      (node (ref "R1") (pin "1") (pinfunction "1_1") (pintype "passive"))
    )
    (net (code "160") (name "unconnected-(R1-Pad2)") (class "Default")
      (node (ref "R1") (pin "2") (pinfunction "2_2") (pintype "passive"))
    )
    (net (code "161") (name "unconnected-(R1-Pad3)") (class "Default")
      (node (ref "R1") (pin "3") (pinfunction "3_3") (pintype "passive"))
    )
    (net (code "162") (name "unconnected-(R1-Pad4)") (class "Default")
      (node (ref "R1") (pin "4") (pinfunction "4_4") (pintype "passive"))
    )
    (net (code "163") (name "unconnected-(R1-Pad5)") (class "Default")
      (node (ref "R1") (pin "5") (pinfunction "5_5") (pintype "passive"))
    )
    (net (code "164") (name "unconnected-(R1-Pad6)") (class "Default")
      (node (ref "R1") (pin "6") (pinfunction "6_6") (pintype "passive"))
    )
    (net (code "165") (name "unconnected-(R1-Pad7)") (class "Default")
      (node (ref "R1") (pin "7") (pinfunction "7_7") (pintype "passive"))
    )
    (net (code "166") (name "unconnected-(R1-Pad8)") (class "Default")
      (node (ref "R1") (pin "8") (pinfunction "8_8") (pintype "passive"))
    )
    (net (code "167") (name "unconnected-(R4-Pad1)") (class "Default")
      (node (ref "R4") (pin "1") (pinfunction "1_1") (pintype "passive"))
    )
    (net (code "168") (name "unconnected-(R4-Pad2)") (class "Default")
      (node (ref "R4") (pin "2") (pinfunction "2_2") (pintype "passive"))
    )
    (net (code "169") (name "unconnected-(R4-Pad3)") (class "Default")
      (node (ref "R4") (pin "3") (pinfunction "3_3") (pintype "passive"))
    )
    (net (code "170") (name "unconnected-(R4-Pad4)") (class "Default")
      (node (ref "R4") (pin "4") (pinfunction "4_4") (pintype "passive"))
    )
    (net (code "171") (name "unconnected-(R4-Pad5)") (class "Default")
      (node (ref "R4") (pin "5") (pinfunction "5_5") (pintype "passive"))
    )
    (net (code "172") (name "unconnected-(R4-Pad6)") (class "Default")
      (node (ref "R4") (pin "6") (pinfunction "6_6") (pintype "passive"))
    )
    (net (code "173") (name "unconnected-(R4-Pad7)") (class "Default")
      (node (ref "R4") (pin "7") (pinfunction "7_7") (pintype "passive"))
    )
    (net (code "174") (name "unconnected-(R4-Pad8)") (class "Default")
      (node (ref "R4") (pin "8") (pinfunction "8_8") (pintype "passive"))
    )
    (net (code "175") (name "unconnected-(S1-Pad1)") (class "Default")
      (node (ref "S1") (pin "1") (pinfunction "1_1") (pintype "passive"))
    )
    (net (code "176") (name "unconnected-(S2-Pad1)") (class "Default")
      (node (ref "S2") (pin "1") (pinfunction "1_1") (pintype "passive"))
    )
    (net (code "177") (name "unconnected-(S3-Pad1)") (class "Default")
      (node (ref "S3") (pin "1") (pinfunction "1_1") (pintype "passive"))
    )
    (net (code "178") (name "unconnected-(S4-Pad1)") (class "Default")
      (node (ref "S4") (pin "1") (pinfunction "1_1") (pintype "passive"))
    )
    (net (code "179") (name "unconnected-(S5-Pad1)") (class "Default")
      (node (ref "S5") (pin "1") (pinfunction "1_1") (pintype "passive"))
    )
    (net (code "180") (name "unconnected-(U1-ALE-Pad30)") (class "Default")
      (node (ref "U1") (pin "30") (pinfunction "ALE_30") (pintype "output"))
    )
    (net (code "181") (name "unconnected-(U1-P0.0{slash}AD0-Pad39)") (class "Default")
      (node (ref "U1") (pin "39") (pinfunction "P0.0/AD0_39") (pintype "bidirectional"))
    )
    (net (code "182") (name "unconnected-(U1-P0.1{slash}AD1-Pad38)") (class "Default")
      (node (ref "U1") (pin "38") (pinfunction "P0.1/AD1_38") (pintype "bidirectional"))
    )
    (net (code "183") (name "unconnected-(U1-P0.2{slash}AD2-Pad37)") (class "Default")
      (node (ref "U1") (pin "37") (pinfunction "P0.2/AD2_37") (pintype "bidirectional"))
    )
    (net (code "184") (name "unconnected-(U1-P0.3{slash}AD3-Pad36)") (class "Default")
      (node (ref "U1") (pin "36") (pinfunction "P0.3/AD3_36") (pintype "bidirectional"))
    )
    (net (code "185") (name "unconnected-(U1-P0.4{slash}AD4-Pad35)") (class "Default")
      (node (ref "U1") (pin "35") (pinfunction "P0.4/AD4_35") (pintype "bidirectional"))
    )
    (net (code "186") (name "unconnected-(U1-P0.5{slash}AD5-Pad34)") (class "Default")
      (node (ref "U1") (pin "34") (pinfunction "P0.5/AD5_34") (pintype "bidirectional"))
    )
    (net (code "187") (name "unconnected-(U1-P0.6{slash}AD6-Pad33)") (class "Default")
      (node (ref "U1") (pin "33") (pinfunction "P0.6/AD6_33") (pintype "bidirectional"))
    )
    (net (code "188") (name "unconnected-(U1-P0.7{slash}AD7-Pad32)") (class "Default")
      (node (ref "U1") (pin "32") (pinfunction "P0.7/AD7_32") (pintype "bidirectional"))
    )
    (net (code "189") (name "unconnected-(U1-P1.0{slash}T2-Pad1)") (class "Default")
      (node (ref "U1") (pin "1") (pinfunction "P1.0/T2_1") (pintype "bidirectional"))
    )
    (net (code "190") (name "unconnected-(U1-P1.1{slash}T2EX-Pad2)") (class "Default")
      (node (ref "U1") (pin "2") (pinfunction "P1.1/T2EX_2") (pintype "bidirectional"))
    )
    (net (code "191") (name "unconnected-(U1-P1.2-Pad3)") (class "Default")
      (node (ref "U1") (pin "3") (pinfunction "P1.2_3") (pintype "bidirectional"))
    )
    (net (code "192") (name "unconnected-(U1-P1.3-Pad4)") (class "Default")
      (node (ref "U1") (pin "4") (pinfunction "P1.3_4") (pintype "bidirectional"))
    )
    (net (code "193") (name "unconnected-(U1-P1.4-Pad5)") (class "Default")
      (node (ref "U1") (pin "5") (pinfunction "P1.4_5") (pintype "bidirectional"))
    )
    (net (code "194") (name "unconnected-(U1-P1.5-Pad6)") (class "Default")
      (node (ref "U1") (pin "6") (pinfunction "P1.5_6") (pintype "bidirectional"))
    )
    (net (code "195") (name "unconnected-(U1-P1.6-Pad7)") (class "Default")
      (node (ref "U1") (pin "7") (pinfunction "P1.6_7") (pintype "bidirectional"))
    )
    (net (code "196") (name "unconnected-(U1-P2.0{slash}A8-Pad21)") (class "Default")
      (node (ref "U1") (pin "21") (pinfunction "P2.0/A8_21") (pintype "bidirectional"))
    )
    (net (code "197") (name "unconnected-(U1-P2.1{slash}A9-Pad22)") (class "Default")
      (node (ref "U1") (pin "22") (pinfunction "P2.1/A9_22") (pintype "bidirectional"))
    )
    (net (code "198") (name "unconnected-(U1-P2.2{slash}A10-Pad23)") (class "Default")
      (node (ref "U1") (pin "23") (pinfunction "P2.2/A10_23") (pintype "bidirectional"))
    )
    (net (code "199") (name "unconnected-(U1-P2.3{slash}A11-Pad24)") (class "Default")
      (node (ref "U1") (pin "24") (pinfunction "P2.3/A11_24") (pintype "bidirectional"))
    )
    (net (code "200") (name "unconnected-(U1-P2.4{slash}A12-Pad25)") (class "Default")
      (node (ref "U1") (pin "25") (pinfunction "P2.4/A12_25") (pintype "bidirectional"))
    )
    (net (code "201") (name "unconnected-(U1-P2.5{slash}A13-Pad26)") (class "Default")
      (node (ref "U1") (pin "26") (pinfunction "P2.5/A13_26") (pintype "bidirectional"))
    )
    (net (code "202") (name "unconnected-(U1-P2.6{slash}A14-Pad27)") (class "Default")
      (node (ref "U1") (pin "27") (pinfunction "P2.6/A14_27") (pintype "bidirectional"))
    )
    (net (code "203") (name "unconnected-(U1-P2.7{slash}A15-Pad28)") (class "Default")
      (node (ref "U1") (pin "28") (pinfunction "P2.7/A15_28") (pintype "bidirectional"))
    )
    (net (code "204") (name "unconnected-(U1-P3.0{slash}RxD-Pad10)") (class "Default")
      (node (ref "U1") (pin "10") (pinfunction "P3.0/RxD_10") (pintype "bidirectional"))
    )
    (net (code "205") (name "unconnected-(U1-P3.1{slash}TxD-Pad11)") (class "Default")
      (node (ref "U1") (pin "11") (pinfunction "P3.1/TxD_11") (pintype "bidirectional"))
    )
    (net (code "206") (name "unconnected-(U1-P3.2{slash}~{INT}0-Pad12)") (class "Default")
      (node (ref "U1") (pin "12") (pinfunction "P3.2/~{INT}0_12") (pintype "bidirectional"))
    )
    (net (code "207") (name "unconnected-(U1-P3.3{slash}~{INT}1-Pad13)") (class "Default")
      (node (ref "U1") (pin "13") (pinfunction "P3.3/~{INT}1_13") (pintype "bidirectional"))
    )
    (net (code "208") (name "unconnected-(U1-P3.4{slash}T0-Pad14)") (class "Default")
      (node (ref "U1") (pin "14") (pinfunction "P3.4/T0_14") (pintype "bidirectional"))
    )
    (net (code "209") (name "unconnected-(U1-P3.5{slash}T1-Pad15)") (class "Default")
      (node (ref "U1") (pin "15") (pinfunction "P3.5/T1_15") (pintype "bidirectional"))
    )
    (net (code "210") (name "unconnected-(U1-P3.6{slash}~{WR}-Pad16)") (class "Default")
      (node (ref "U1") (pin "16") (pinfunction "P3.6/~{WR}_16") (pintype "bidirectional"))
    )
    (net (code "211") (name "unconnected-(U1-P3.7{slash}~{RD}-Pad17)") (class "Default")
      (node (ref "U1") (pin "17") (pinfunction "P3.7/~{RD}_17") (pintype "bidirectional"))
    )
    (net (code "212") (name "unconnected-(U1-~{PSEN}-Pad29)") (class "Default")
      (node (ref "U1") (pin "29") (pinfunction "~{PSEN}_29") (pintype "output"))
    )
    (net (code "213") (name "unconnected-(U2-A-Pad1)") (class "Default")
      (node (ref "U2") (pin "1") (pinfunction "A_1") (pintype "input"))
    )
    (net (code "214") (name "unconnected-(U2-B-Pad2)") (class "Default")
      (node (ref "U2") (pin "2") (pinfunction "B_2") (pintype "input"))
    )
    (net (code "215") (name "unconnected-(U2-C-Pad3)") (class "Default")
      (node (ref "U2") (pin "3") (pinfunction "C_3") (pintype "input"))
    )
    (net (code "216") (name "unconnected-(U3-ALE-Pad30)") (class "Default")
      (node (ref "U3") (pin "30") (pinfunction "ALE_30") (pintype "output"))
    )
    (net (code "217") (name "unconnected-(U3-P0.0{slash}AD0-Pad39)") (class "Default")
      (node (ref "U3") (pin "39") (pinfunction "P0.0/AD0_39") (pintype "bidirectional"))
    )
    (net (code "218") (name "unconnected-(U3-P0.1{slash}AD1-Pad38)") (class "Default")
      (node (ref "U3") (pin "38") (pinfunction "P0.1/AD1_38") (pintype "bidirectional"))
    )
    (net (code "219") (name "unconnected-(U3-P0.2{slash}AD2-Pad37)") (class "Default")
      (node (ref "U3") (pin "37") (pinfunction "P0.2/AD2_37") (pintype "bidirectional"))
    )
    (net (code "220") (name "unconnected-(U3-P0.3{slash}AD3-Pad36)") (class "Default")
      (node (ref "U3") (pin "36") (pinfunction "P0.3/AD3_36") (pintype "bidirectional"))
    )
    (net (code "221") (name "unconnected-(U3-P0.4{slash}AD4-Pad35)") (class "Default")
      (node (ref "U3") (pin "35") (pinfunction "P0.4/AD4_35") (pintype "bidirectional"))
    )
    (net (code "222") (name "unconnected-(U3-P0.5{slash}AD5-Pad34)") (class "Default")
      (node (ref "U3") (pin "34") (pinfunction "P0.5/AD5_34") (pintype "bidirectional"))
    )
    (net (code "223") (name "unconnected-(U3-P0.6{slash}AD6-Pad33)") (class "Default")
      (node (ref "U3") (pin "33") (pinfunction "P0.6/AD6_33") (pintype "bidirectional"))
    )
    (net (code "224") (name "unconnected-(U3-P0.7{slash}AD7-Pad32)") (class "Default")
      (node (ref "U3") (pin "32") (pinfunction "P0.7/AD7_32") (pintype "bidirectional"))
    )
    (net (code "225") (name "unconnected-(U3-P1.0{slash}T2-Pad1)") (class "Default")
      (node (ref "U3") (pin "1") (pinfunction "P1.0/T2_1") (pintype "bidirectional"))
    )
    (net (code "226") (name "unconnected-(U3-P1.1{slash}T2EX-Pad2)") (class "Default")
      (node (ref "U3") (pin "2") (pinfunction "P1.1/T2EX_2") (pintype "bidirectional"))
    )
    (net (code "227") (name "unconnected-(U3-P1.2-Pad3)") (class "Default")
      (node (ref "U3") (pin "3") (pinfunction "P1.2_3") (pintype "bidirectional"))
    )
    (net (code "228") (name "unconnected-(U3-P1.3-Pad4)") (class "Default")
      (node (ref "U3") (pin "4") (pinfunction "P1.3_4") (pintype "bidirectional"))
    )
    (net (code "229") (name "unconnected-(U3-P1.4-Pad5)") (class "Default")
      (node (ref "U3") (pin "5") (pinfunction "P1.4_5") (pintype "bidirectional"))
    )
    (net (code "230") (name "unconnected-(U3-P1.5-Pad6)") (class "Default")
      (node (ref "U3") (pin "6") (pinfunction "P1.5_6") (pintype "bidirectional"))
    )
    (net (code "231") (name "unconnected-(U3-P1.6-Pad7)") (class "Default")
      (node (ref "U3") (pin "7") (pinfunction "P1.6_7") (pintype "bidirectional"))
    )
    (net (code "232") (name "unconnected-(U3-P1.7-Pad8)") (class "Default")
      (node (ref "U3") (pin "8") (pinfunction "P1.7_8") (pintype "bidirectional"))
    )
    (net (code "233") (name "unconnected-(U3-P2.0{slash}A8-Pad21)") (class "Default")
      (node (ref "U3") (pin "21") (pinfunction "P2.0/A8_21") (pintype "bidirectional"))
    )
    (net (code "234") (name "unconnected-(U3-P2.1{slash}A9-Pad22)") (class "Default")
      (node (ref "U3") (pin "22") (pinfunction "P2.1/A9_22") (pintype "bidirectional"))
    )
    (net (code "235") (name "unconnected-(U3-P2.2{slash}A10-Pad23)") (class "Default")
      (node (ref "U3") (pin "23") (pinfunction "P2.2/A10_23") (pintype "bidirectional"))
    )
    (net (code "236") (name "unconnected-(U3-P2.3{slash}A11-Pad24)") (class "Default")
      (node (ref "U3") (pin "24") (pinfunction "P2.3/A11_24") (pintype "bidirectional"))
    )
    (net (code "237") (name "unconnected-(U3-P2.4{slash}A12-Pad25)") (class "Default")
      (node (ref "U3") (pin "25") (pinfunction "P2.4/A12_25") (pintype "bidirectional"))
    )
    (net (code "238") (name "unconnected-(U3-P2.5{slash}A13-Pad26)") (class "Default")
      (node (ref "U3") (pin "26") (pinfunction "P2.5/A13_26") (pintype "bidirectional"))
    )
    (net (code "239") (name "unconnected-(U3-P2.6{slash}A14-Pad27)") (class "Default")
      (node (ref "U3") (pin "27") (pinfunction "P2.6/A14_27") (pintype "bidirectional"))
    )
    (net (code "240") (name "unconnected-(U3-P2.7{slash}A15-Pad28)") (class "Default")
      (node (ref "U3") (pin "28") (pinfunction "P2.7/A15_28") (pintype "bidirectional"))
    )
    (net (code "241") (name "unconnected-(U3-P3.0{slash}RxD-Pad10)") (class "Default")
      (node (ref "U3") (pin "10") (pinfunction "P3.0/RxD_10") (pintype "bidirectional"))
    )
    (net (code "242") (name "unconnected-(U3-P3.2{slash}~{INT}0-Pad12)") (class "Default")
      (node (ref "U3") (pin "12") (pinfunction "P3.2/~{INT}0_12") (pintype "bidirectional"))
    )
    (net (code "243") (name "unconnected-(U3-P3.3{slash}~{INT}1-Pad13)") (class "Default")
      (node (ref "U3") (pin "13") (pinfunction "P3.3/~{INT}1_13") (pintype "bidirectional"))
    )
    (net (code "244") (name "unconnected-(U3-P3.4{slash}T0-Pad14)") (class "Default")
      (node (ref "U3") (pin "14") (pinfunction "P3.4/T0_14") (pintype "bidirectional"))
    )
    (net (code "245") (name "unconnected-(U3-P3.5{slash}T1-Pad15)") (class "Default")
      (node (ref "U3") (pin "15") (pinfunction "P3.5/T1_15") (pintype "bidirectional"))
    )
    (net (code "246") (name "unconnected-(U3-P3.6{slash}~{WR}-Pad16)") (class "Default")
      (node (ref "U3") (pin "16") (pinfunction "P3.6/~{WR}_16") (pintype "bidirectional"))
    )
    (net (code "247") (name "unconnected-(U3-P3.7{slash}~{RD}-Pad17)") (class "Default")
      (node (ref "U3") (pin "17") (pinfunction "P3.7/~{RD}_17") (pintype "bidirectional"))
    )
    (net (code "248") (name "unconnected-(U3-~{PSEN}-Pad29)") (class "Default")
      (node (ref "U3") (pin "29") (pinfunction "~{PSEN}_29") (pintype "output"))
    )
  )
)
